# schematic.net
KiCad netlist of a schematic drawn in EAGLE
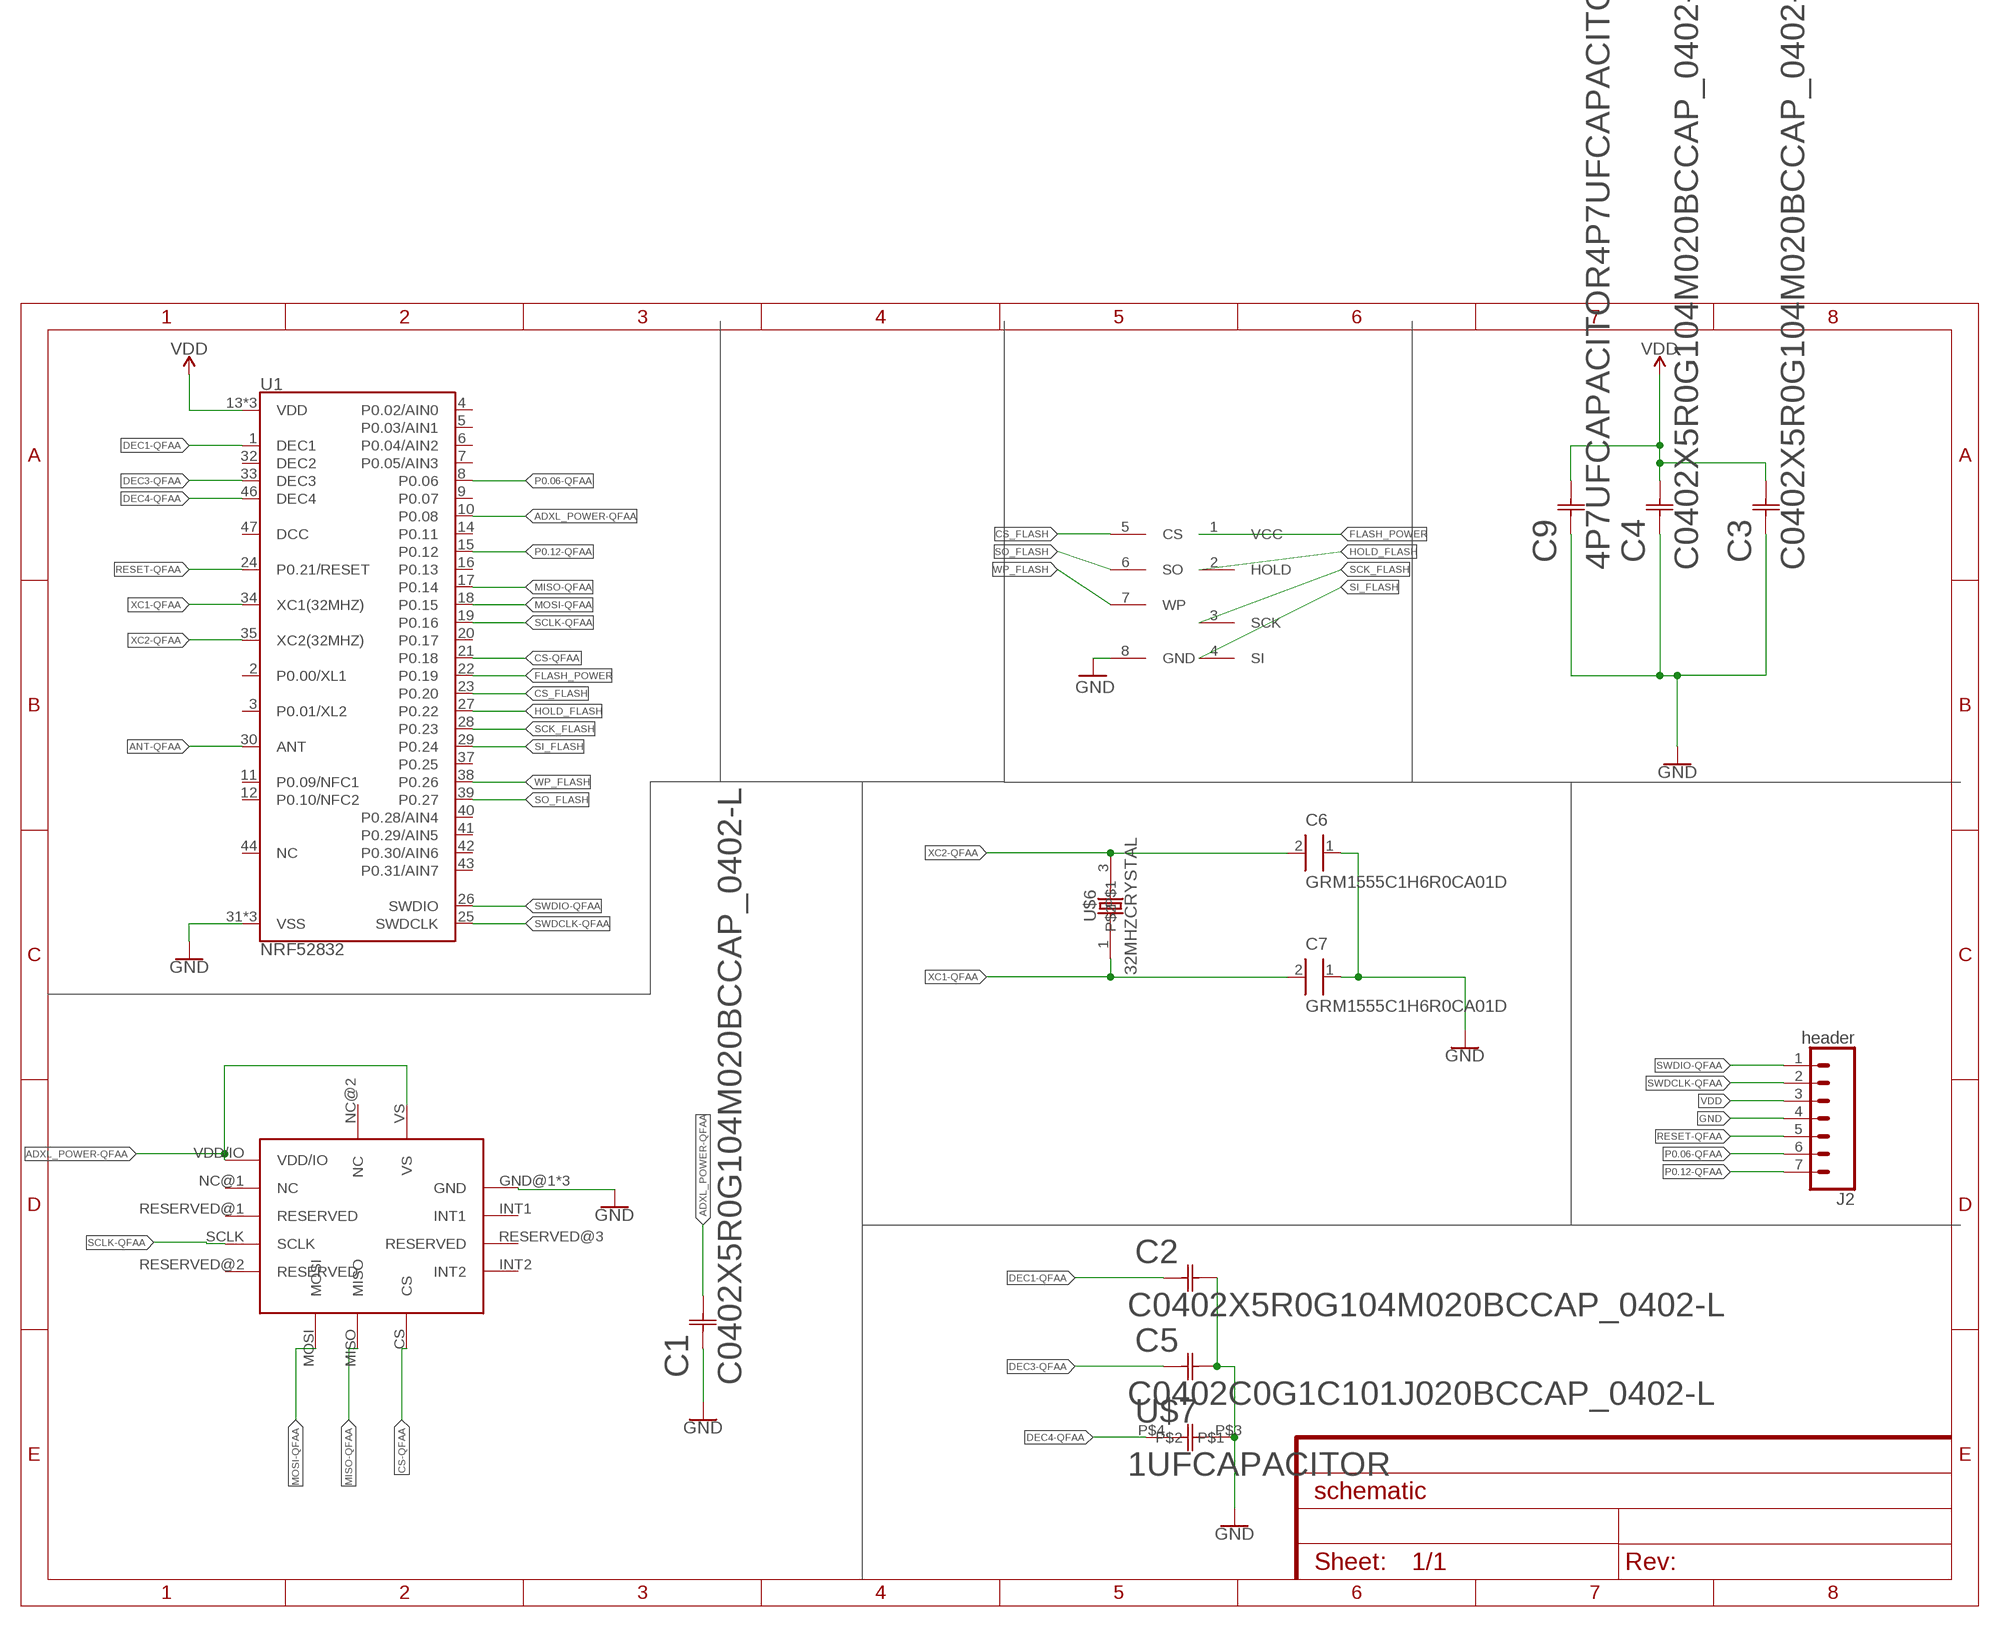
[diagram p0: schematic, sheet 1]

(export (version "E")
  (design (tool "Eeschema 10.0.6"))
  (components
    (comp (ref "C1")
      (value "C0402X5R0G104M020BCCAP_0402-L")
      (footprint "eagle-import:CAP_0402-L")
      (fields (field (name "MANUFACTURER_PART_NUMBER") "C0402C0G1C101J020BC"))
      (libsource (lib "eagle-import") (part "C0402X5R0G104M020BCCAP_0402-L"))
    )
    (comp (ref "C2")
      (value "C0402X5R0G104M020BCCAP_0402-L")
      (footprint "eagle-import:CAP_0402-L")
      (fields (field (name "MANUFACTURER_PART_NUMBER") "C0402C0G1C101J020BC"))
      (libsource (lib "eagle-import") (part "C0402X5R0G104M020BCCAP_0402-L"))
    )
    (comp (ref "C3")
      (value "C0402X5R0G104M020BCCAP_0402-L")
      (footprint "eagle-import:CAP_0402-L")
      (fields (field (name "MANUFACTURER_PART_NUMBER") "C0402C0G1C101J020BC"))
      (libsource (lib "eagle-import") (part "C0402X5R0G104M020BCCAP_0402-L"))
    )
    (comp (ref "C4")
      (value "C0402X5R0G104M020BCCAP_0402-L")
      (footprint "eagle-import:CAP_0402-L")
      (fields (field (name "MANUFACTURER_PART_NUMBER") "C0402C0G1C101J020BC"))
      (libsource (lib "eagle-import") (part "C0402X5R0G104M020BCCAP_0402-L"))
    )
    (comp (ref "C5")
      (value "C0402C0G1C101J020BCCAP_0402-L")
      (footprint "eagle-import:CAP_0402-L")
      (fields (field (name "MANUFACTURER_PART_NUMBER") "C0402C0G1C101J020BC"))
      (libsource (lib "eagle-import") (part "C0402C0G1C101J020BCCAP_0402-L"))
    )
    (comp (ref "C6")
      (value "GRM1555C1H6R0CA01D")
      (footprint "eagle-import:CAPC1005X55N")
      (fields (field (name "DIGI-KEY_PART_NUMBER") "490-8222-1-ND") (field (name "MF") "Murata"))
      (libsource (lib "eagle-import") (part "GRM1555C1H6R0CA01D"))
    )
    (comp (ref "C7")
      (value "GRM1555C1H6R0CA01D")
      (footprint "eagle-import:CAPC1005X55N")
      (fields (field (name "DIGI-KEY_PART_NUMBER") "490-8222-1-ND") (field (name "MF") "Murata"))
      (libsource (lib "eagle-import") (part "GRM1555C1H6R0CA01D"))
    )
    (comp (ref "C9")
      (value "4P7UFCAPACITOR4P7UFCAPACITOR")
      (footprint "eagle-import:4P7UFCAPACITOR")
      (fields (field (name "MANUFACTURER_PART_NUMBER") "C0816X5R0J475M050AC"))
      (libsource (lib "eagle-import") (part "4P7UFCAPACITOR4P7UFCAPACITOR"))
    )
    (comp (ref "J2")
      (value "header")
      (footprint "eagle-import:1X07")
      (libsource (lib "eagle-import") (part "CONN_07"))
    )
    (comp (ref "U$1")
      (value "ADXL362")
      (footprint "eagle-import:TFLGA-16_3.3MMX3.1MM")
      (libsource (lib "eagle-import") (part "ADXL362"))
    )
    (comp (ref "U$3")
      (value "AT25SF161-UUD-T")
      (footprint "eagle-import:AT25SF161-UUD-T")
      (libsource (lib "eagle-import") (part "AT25SF161-UUD-T"))
    )
    (comp (ref "U$6")
      (value "32MHZCRYSTAL")
      (footprint "eagle-import:32MHZCRYSTAL")
      (libsource (lib "eagle-import") (part "32MHZCRYSTAL"))
    )
    (comp (ref "U$7")
      (value "1UFCAPACITOR")
      (footprint "eagle-import:1UFCAPACITOR")
      (libsource (lib "eagle-import") (part "1UFCAPACITOR"))
    )
    (comp (ref "U1")
      (value "NRF52832")
      (footprint "eagle-import:QFN48-6X6MM")
      (libsource (lib "eagle-import") (part "NRF52832"))
    )
  )
  (nets
    (net (code "1") (name "ADXL_POWER-QFAA") (class "Default")
      (node (ref "C1") (pin "2") (pinfunction "22_2") (pintype "passive"))
      (node (ref "U$1") (pin "VDD/IO") (pinfunction "VDD/IO_VDD/IO") (pintype "bidirectional"))
      (node (ref "U$1") (pin "VS") (pinfunction "VS_VS") (pintype "bidirectional"))
      (node (ref "U1") (pin "10") (pinfunction "P0.08_10") (pintype "bidirectional"))
    )
    (net (code "2") (name "ANT-QFAA") (class "Default")
      (node (ref "U1") (pin "30") (pinfunction "ANT_30") (pintype "bidirectional"))
    )
    (net (code "3") (name "CS-QFAA") (class "Default")
      (node (ref "U$1") (pin "CS") (pinfunction "CS_CS") (pintype "bidirectional"))
      (node (ref "U1") (pin "21") (pinfunction "P0.18_21") (pintype "bidirectional"))
    )
    (net (code "4") (name "CS_FLASH") (class "Default")
      (node (ref "U$3") (pin "5") (pinfunction "CS_5") (pintype "input"))
      (node (ref "U1") (pin "23") (pinfunction "P0.20_23") (pintype "bidirectional"))
    )
    (net (code "5") (name "DEC1-QFAA") (class "Default")
      (node (ref "C2") (pin "1") (pinfunction "11_1") (pintype "passive"))
      (node (ref "U1") (pin "1") (pinfunction "DEC1_1") (pintype "bidirectional"))
    )
    (net (code "6") (name "DEC3-QFAA") (class "Default")
      (node (ref "C5") (pin "1") (pinfunction "11_1") (pintype "passive"))
      (node (ref "U1") (pin "33") (pinfunction "DEC3_33") (pintype "bidirectional"))
    )
    (net (code "7") (name "DEC4-QFAA") (class "Default")
      (node (ref "U$7") (pin "P$4") (pinfunction "P$1_P$4") (pintype "bidirectional"))
      (node (ref "U1") (pin "46") (pinfunction "DEC4_46") (pintype "bidirectional"))
    )
    (net (code "8") (name "FLASH_POWER") (class "Default")
      (node (ref "U$3") (pin "1") (pinfunction "VCC_1") (pintype "power_in"))
      (node (ref "U1") (pin "22") (pinfunction "P0.19_22") (pintype "bidirectional"))
    )
    (net (code "9") (name "GND") (class "Default")
      (node (ref "C1") (pin "1") (pinfunction "11_1") (pintype "passive"))
      (node (ref "C2") (pin "2") (pinfunction "22_2") (pintype "passive"))
      (node (ref "C3") (pin "1") (pinfunction "11_1") (pintype "passive"))
      (node (ref "C4") (pin "1") (pinfunction "11_1") (pintype "passive"))
      (node (ref "C5") (pin "2") (pinfunction "22_2") (pintype "passive"))
      (node (ref "C6") (pin "1") (pinfunction "1_1") (pintype "passive"))
      (node (ref "C7") (pin "1") (pinfunction "1_1") (pintype "passive"))
      (node (ref "C9") (pin "1") (pinfunction "11_1") (pintype "passive"))
      (node (ref "J2") (pin "4") (pinfunction "4_4") (pintype "passive"))
      (node (ref "U$1") (pin "GND@1") (pinfunction "GND_GND@1") (pintype "bidirectional"))
      (node (ref "U$1") (pin "GND@2") (pinfunction "GND_GND@2") (pintype "bidirectional"))
      (node (ref "U$1") (pin "GND@3") (pinfunction "GND_GND@3") (pintype "bidirectional"))
      (node (ref "U$3") (pin "8") (pinfunction "GND_8") (pintype "power_in"))
      (node (ref "U$7") (pin "P$3") (pinfunction "P$2_P$3") (pintype "bidirectional"))
      (node (ref "U1") (pin "31") (pinfunction "VSS_31") (pintype "bidirectional"))
      (node (ref "U1") (pin "45") (pinfunction "VSS_45") (pintype "bidirectional"))
      (node (ref "U1") (pin "EP") (pinfunction "VSS_EP") (pintype "bidirectional"))
    )
    (net (code "10") (name "HOLD_FLASH") (class "Default")
      (node (ref "U$3") (pin "2") (pinfunction "HOLD_2") (pintype "bidirectional"))
      (node (ref "U1") (pin "27") (pinfunction "P0.22_27") (pintype "bidirectional"))
    )
    (net (code "11") (name "MISO-QFAA") (class "Default")
      (node (ref "U$1") (pin "MISO") (pinfunction "MISO_MISO") (pintype "bidirectional"))
      (node (ref "U1") (pin "17") (pinfunction "P0.14_17") (pintype "bidirectional"))
    )
    (net (code "12") (name "MOSI-QFAA") (class "Default")
      (node (ref "U$1") (pin "MOSI") (pinfunction "MOSI_MOSI") (pintype "bidirectional"))
      (node (ref "U1") (pin "18") (pinfunction "P0.15_18") (pintype "bidirectional"))
    )
    (net (code "13") (name "P0.06-QFAA") (class "Default")
      (node (ref "J2") (pin "6") (pinfunction "6_6") (pintype "passive"))
      (node (ref "U1") (pin "8") (pinfunction "P0.06_8") (pintype "bidirectional"))
    )
    (net (code "14") (name "P0.12-QFAA") (class "Default")
      (node (ref "J2") (pin "7") (pinfunction "7_7") (pintype "passive"))
      (node (ref "U1") (pin "15") (pinfunction "P0.12_15") (pintype "bidirectional"))
    )
    (net (code "15") (name "RESET-QFAA") (class "Default")
      (node (ref "J2") (pin "5") (pinfunction "5_5") (pintype "passive"))
      (node (ref "U1") (pin "24") (pinfunction "P0.21/RESET_24") (pintype "bidirectional"))
    )
    (net (code "16") (name "SCK_FLASH") (class "Default")
      (node (ref "U$3") (pin "3") (pinfunction "SCK_3") (pintype "input"))
      (node (ref "U1") (pin "28") (pinfunction "P0.23_28") (pintype "bidirectional"))
    )
    (net (code "17") (name "SCLK-QFAA") (class "Default")
      (node (ref "U$1") (pin "SCLK") (pinfunction "SCLK_SCLK") (pintype "bidirectional"))
      (node (ref "U1") (pin "19") (pinfunction "P0.16_19") (pintype "bidirectional"))
    )
    (net (code "18") (name "SI_FLASH") (class "Default")
      (node (ref "U$3") (pin "4") (pinfunction "SI_4") (pintype "bidirectional"))
      (node (ref "U1") (pin "29") (pinfunction "P0.24_29") (pintype "bidirectional"))
    )
    (net (code "19") (name "SO_FLASH") (class "Default")
      (node (ref "U$3") (pin "6") (pinfunction "SO_6") (pintype "bidirectional"))
      (node (ref "U1") (pin "39") (pinfunction "P0.27_39") (pintype "bidirectional"))
    )
    (net (code "20") (name "SWDCLK-QFAA") (class "Default")
      (node (ref "J2") (pin "2") (pinfunction "2_2") (pintype "passive"))
      (node (ref "U1") (pin "25") (pinfunction "SWDCLK_25") (pintype "bidirectional"))
    )
    (net (code "21") (name "SWDIO-QFAA") (class "Default")
      (node (ref "J2") (pin "1") (pinfunction "1_1") (pintype "passive"))
      (node (ref "U1") (pin "26") (pinfunction "SWDIO_26") (pintype "bidirectional"))
    )
    (net (code "22") (name "VDD") (class "Default")
      (node (ref "C3") (pin "2") (pinfunction "22_2") (pintype "passive"))
      (node (ref "C4") (pin "2") (pinfunction "22_2") (pintype "passive"))
      (node (ref "C9") (pin "2") (pinfunction "22_2") (pintype "passive"))
      (node (ref "J2") (pin "3") (pinfunction "3_3") (pintype "passive"))
      (node (ref "U1") (pin "13") (pinfunction "VDD_13") (pintype "bidirectional"))
      (node (ref "U1") (pin "36") (pinfunction "VDD_36") (pintype "bidirectional"))
      (node (ref "U1") (pin "48") (pinfunction "VDD_48") (pintype "bidirectional"))
    )
    (net (code "23") (name "WP_FLASH") (class "Default")
      (node (ref "U$3") (pin "7") (pinfunction "WP_7") (pintype "bidirectional"))
      (node (ref "U1") (pin "38") (pinfunction "P0.26_38") (pintype "bidirectional"))
    )
    (net (code "24") (name "XC1-QFAA") (class "Default")
      (node (ref "C7") (pin "2") (pinfunction "2_2") (pintype "passive"))
      (node (ref "U$6") (pin "1") (pinfunction "P$1_1") (pintype "bidirectional"))
      (node (ref "U1") (pin "34") (pinfunction "XC1(32MHZ)_34") (pintype "bidirectional"))
    )
    (net (code "25") (name "XC2-QFAA") (class "Default")
      (node (ref "C6") (pin "2") (pinfunction "2_2") (pintype "passive"))
      (node (ref "U$6") (pin "3") (pinfunction "P$2_3") (pintype "bidirectional"))
      (node (ref "U1") (pin "35") (pinfunction "XC2(32MHZ)_35") (pintype "bidirectional"))
    )
    (net (code "26") (name "unconnected-(U$1-NC-PadNC@1)") (class "Default")
      (node (ref "U$1") (pin "NC@1") (pinfunction "NC_NC@1") (pintype "bidirectional"))
    )
    (net (code "27") (name "unconnected-(U$1-NC-PadNC@2)") (class "Default")
      (node (ref "U$1") (pin "NC@2") (pinfunction "NC_NC@2") (pintype "bidirectional"))
    )
    (net (code "28") (name "unconnected-(U$1-PadINT1)") (class "Default")
      (node (ref "U$1") (pin "INT1") (pinfunction "INT1_INT1") (pintype "bidirectional"))
    )
    (net (code "29") (name "unconnected-(U$1-PadINT2)") (class "Default")
      (node (ref "U$1") (pin "INT2") (pinfunction "INT2_INT2") (pintype "bidirectional"))
    )
    (net (code "30") (name "unconnected-(U$1-RESERVED-PadRESERVED@1)") (class "Default")
      (node (ref "U$1") (pin "RESERVED@1") (pinfunction "RESERVED_RESERVED@1") (pintype "bidirectional"))
    )
    (net (code "31") (name "unconnected-(U$1-RESERVED-PadRESERVED@2)") (class "Default")
      (node (ref "U$1") (pin "RESERVED@2") (pinfunction "RESERVED_RESERVED@2") (pintype "bidirectional"))
    )
    (net (code "32") (name "unconnected-(U$1-RESERVED-PadRESERVED@3)") (class "Default")
      (node (ref "U$1") (pin "RESERVED@3") (pinfunction "RESERVED_RESERVED@3") (pintype "bidirectional"))
    )
    (net (code "33") (name "unconnected-(U1-DCC-Pad47)") (class "Default")
      (node (ref "U1") (pin "47") (pinfunction "DCC_47") (pintype "bidirectional"))
    )
    (net (code "34") (name "unconnected-(U1-DEC2-Pad32)") (class "Default")
      (node (ref "U1") (pin "32") (pinfunction "DEC2_32") (pintype "bidirectional"))
    )
    (net (code "35") (name "unconnected-(U1-NC-Pad44)") (class "Default")
      (node (ref "U1") (pin "44") (pinfunction "NC_44") (pintype "bidirectional"))
    )
    (net (code "36") (name "unconnected-(U1-P0.00{slash}XL1-Pad2)") (class "Default")
      (node (ref "U1") (pin "2") (pinfunction "P0.00/XL1_2") (pintype "bidirectional"))
    )
    (net (code "37") (name "unconnected-(U1-P0.01{slash}XL2-Pad3)") (class "Default")
      (node (ref "U1") (pin "3") (pinfunction "P0.01/XL2_3") (pintype "bidirectional"))
    )
    (net (code "38") (name "unconnected-(U1-P0.02{slash}AIN0-Pad4)") (class "Default")
      (node (ref "U1") (pin "4") (pinfunction "P0.02/AIN0_4") (pintype "bidirectional"))
    )
    (net (code "39") (name "unconnected-(U1-P0.03{slash}AIN1-Pad5)") (class "Default")
      (node (ref "U1") (pin "5") (pinfunction "P0.03/AIN1_5") (pintype "bidirectional"))
    )
    (net (code "40") (name "unconnected-(U1-P0.04{slash}AIN2-Pad6)") (class "Default")
      (node (ref "U1") (pin "6") (pinfunction "P0.04/AIN2_6") (pintype "bidirectional"))
    )
    (net (code "41") (name "unconnected-(U1-P0.05{slash}AIN3-Pad7)") (class "Default")
      (node (ref "U1") (pin "7") (pinfunction "P0.05/AIN3_7") (pintype "bidirectional"))
    )
    (net (code "42") (name "unconnected-(U1-P0.07-Pad9)") (class "Default")
      (node (ref "U1") (pin "9") (pinfunction "P0.07_9") (pintype "bidirectional"))
    )
    (net (code "43") (name "unconnected-(U1-P0.09{slash}NFC1-Pad11)") (class "Default")
      (node (ref "U1") (pin "11") (pinfunction "P0.09/NFC1_11") (pintype "bidirectional"))
    )
    (net (code "44") (name "unconnected-(U1-P0.10{slash}NFC2-Pad12)") (class "Default")
      (node (ref "U1") (pin "12") (pinfunction "P0.10/NFC2_12") (pintype "bidirectional"))
    )
    (net (code "45") (name "unconnected-(U1-P0.11-Pad14)") (class "Default")
      (node (ref "U1") (pin "14") (pinfunction "P0.11_14") (pintype "bidirectional"))
    )
    (net (code "46") (name "unconnected-(U1-P0.13-Pad16)") (class "Default")
      (node (ref "U1") (pin "16") (pinfunction "P0.13_16") (pintype "bidirectional"))
    )
    (net (code "47") (name "unconnected-(U1-P0.17-Pad20)") (class "Default")
      (node (ref "U1") (pin "20") (pinfunction "P0.17_20") (pintype "bidirectional"))
    )
    (net (code "48") (name "unconnected-(U1-P0.25-Pad37)") (class "Default")
      (node (ref "U1") (pin "37") (pinfunction "P0.25_37") (pintype "bidirectional"))
    )
    (net (code "49") (name "unconnected-(U1-P0.28{slash}AIN4-Pad40)") (class "Default")
      (node (ref "U1") (pin "40") (pinfunction "P0.28/AIN4_40") (pintype "bidirectional"))
    )
    (net (code "50") (name "unconnected-(U1-P0.29{slash}AIN5-Pad41)") (class "Default")
      (node (ref "U1") (pin "41") (pinfunction "P0.29/AIN5_41") (pintype "bidirectional"))
    )
    (net (code "51") (name "unconnected-(U1-P0.30{slash}AIN6-Pad42)") (class "Default")
      (node (ref "U1") (pin "42") (pinfunction "P0.30/AIN6_42") (pintype "bidirectional"))
    )
    (net (code "52") (name "unconnected-(U1-P0.31{slash}AIN7-Pad43)") (class "Default")
      (node (ref "U1") (pin "43") (pinfunction "P0.31/AIN7_43") (pintype "bidirectional"))
    )
  )
)
